# Solenoid_7.net
KiCad netlist of a schematic drawn in EAGLE
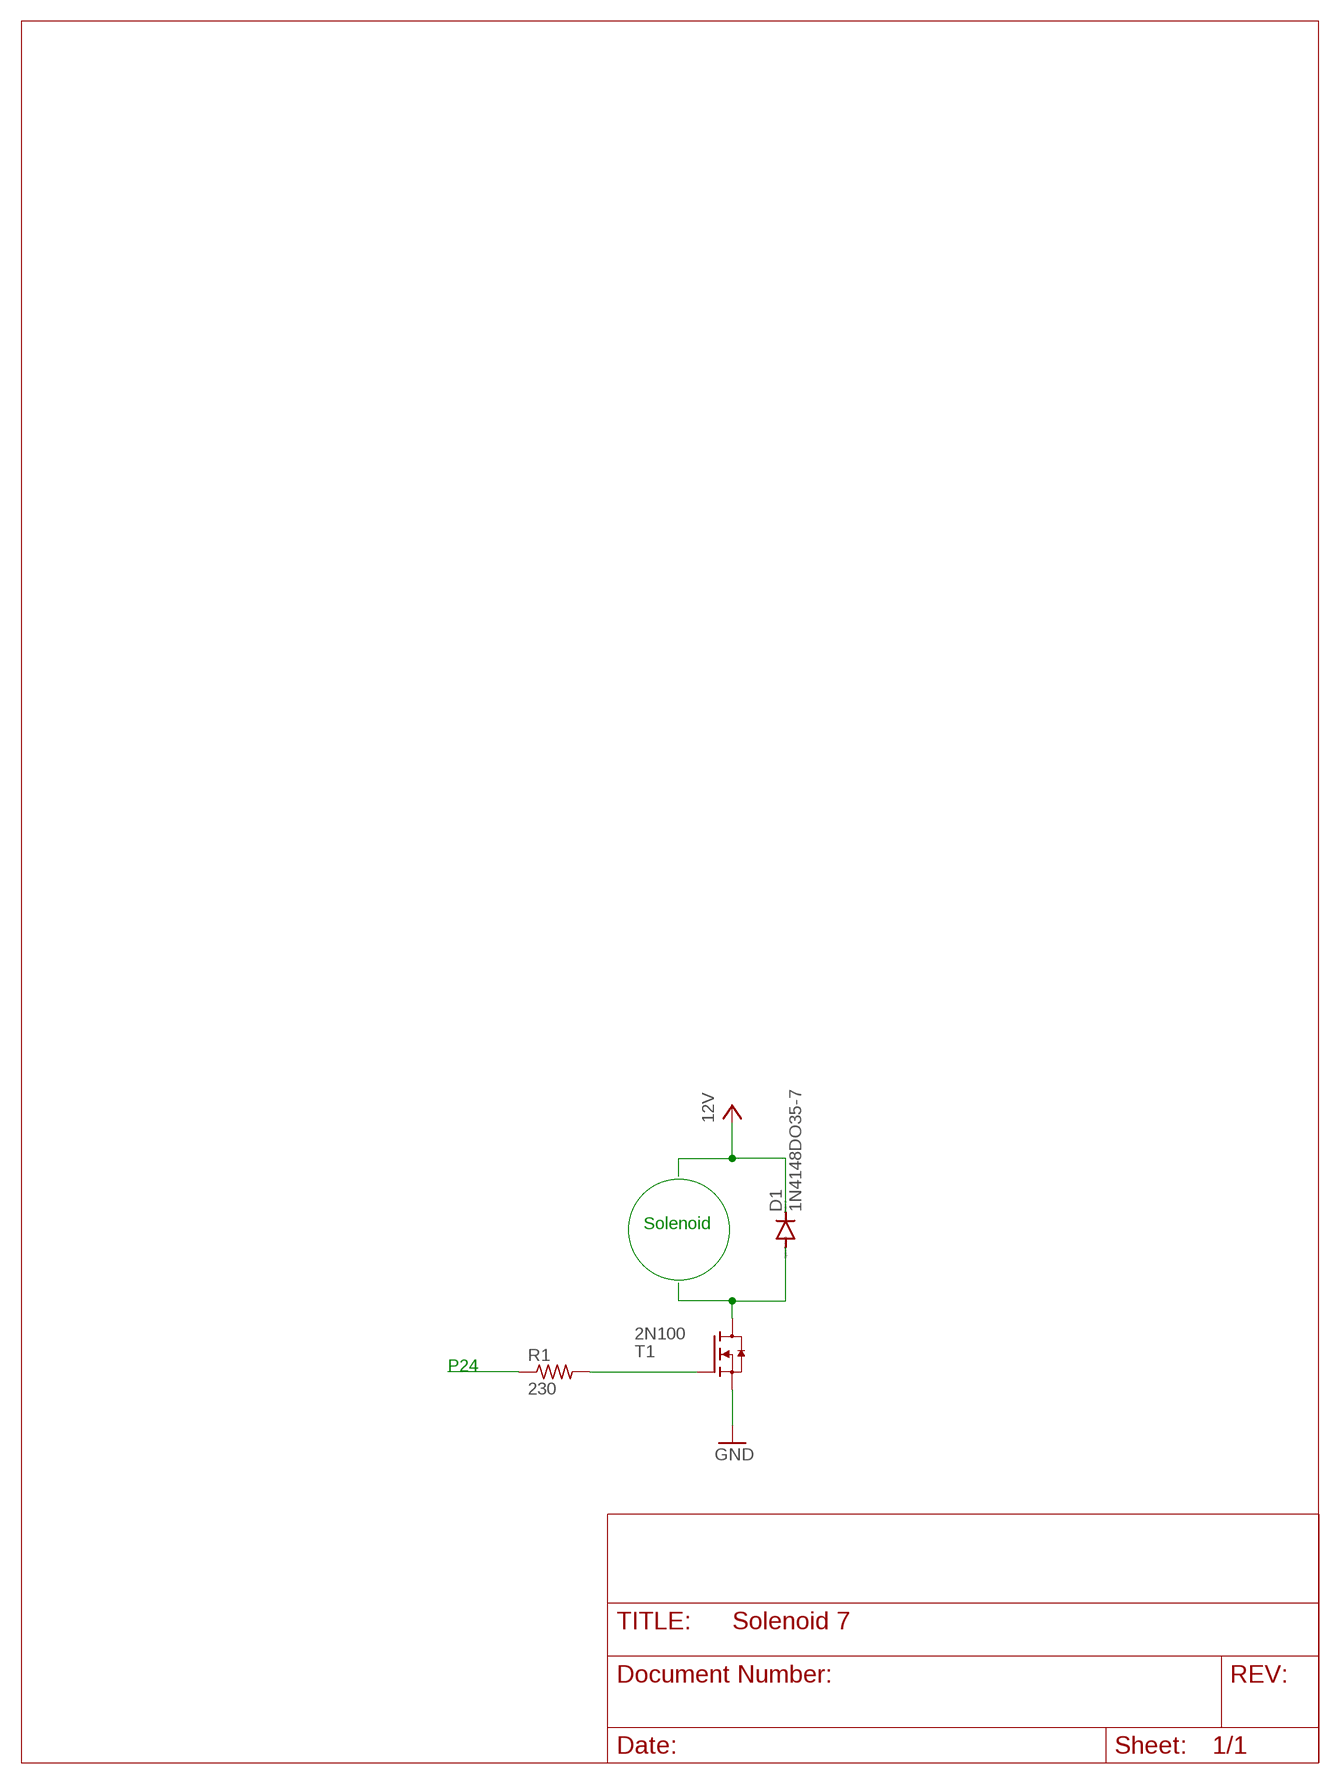
[diagram p0: schematic, sheet 1]

(export (version "E")
  (design (tool "Eeschema 10.0.6"))
  (components
    (comp (ref "D1")
      (value "1N4148DO35-7")
      (footprint "eagle-import:DO35-7")
      (libsource (lib "eagle-import") (part "1N4148DO35-7"))
    )
    (comp (ref "R1")
      (value "230")
      (footprint "eagle-import:0204_7")
      (libsource (lib "eagle-import") (part "R-US_0204/7"))
    )
    (comp (ref "T1")
      (value "2N100")
      (footprint "eagle-import:PG-TO263-7-3")
      (libsource (lib "eagle-import") (part "IPB180N06S4-H1"))
    )
  )
  (nets
    (net (code "1") (name "12V") (class "Default")
      (node (ref "D1") (pin "C") (pinfunction "C_C") (pintype "passive"))
    )
    (net (code "2") (name "GND") (class "Default")
      (node (ref "T1") (pin "2") (pinfunction "S_2") (pintype "passive"))
      (node (ref "T1") (pin "3") (pinfunction "S_3") (pintype "passive"))
      (node (ref "T1") (pin "5") (pinfunction "S_5") (pintype "passive"))
      (node (ref "T1") (pin "6") (pinfunction "S_6") (pintype "passive"))
      (node (ref "T1") (pin "7") (pinfunction "S_7") (pintype "passive"))
    )
    (net (code "3") (name "Net-(T1-D)") (class "Default")
      (node (ref "D1") (pin "A") (pinfunction "A_A") (pintype "passive"))
      (node (ref "T1") (pin "8") (pinfunction "D_8") (pintype "passive"))
    )
    (net (code "4") (name "Net-(T1-G)") (class "Default")
      (node (ref "R1") (pin "2") (pinfunction "2_2") (pintype "passive"))
      (node (ref "T1") (pin "1") (pinfunction "G_1") (pintype "passive"))
    )
    (net (code "5") (name "unconnected-(R1-Pad1)") (class "Default")
      (node (ref "R1") (pin "1") (pinfunction "1_1") (pintype "passive"))
    )
  )
)
